# CT_v02.net
KiCad netlist of a schematic drawn in Altium Designer
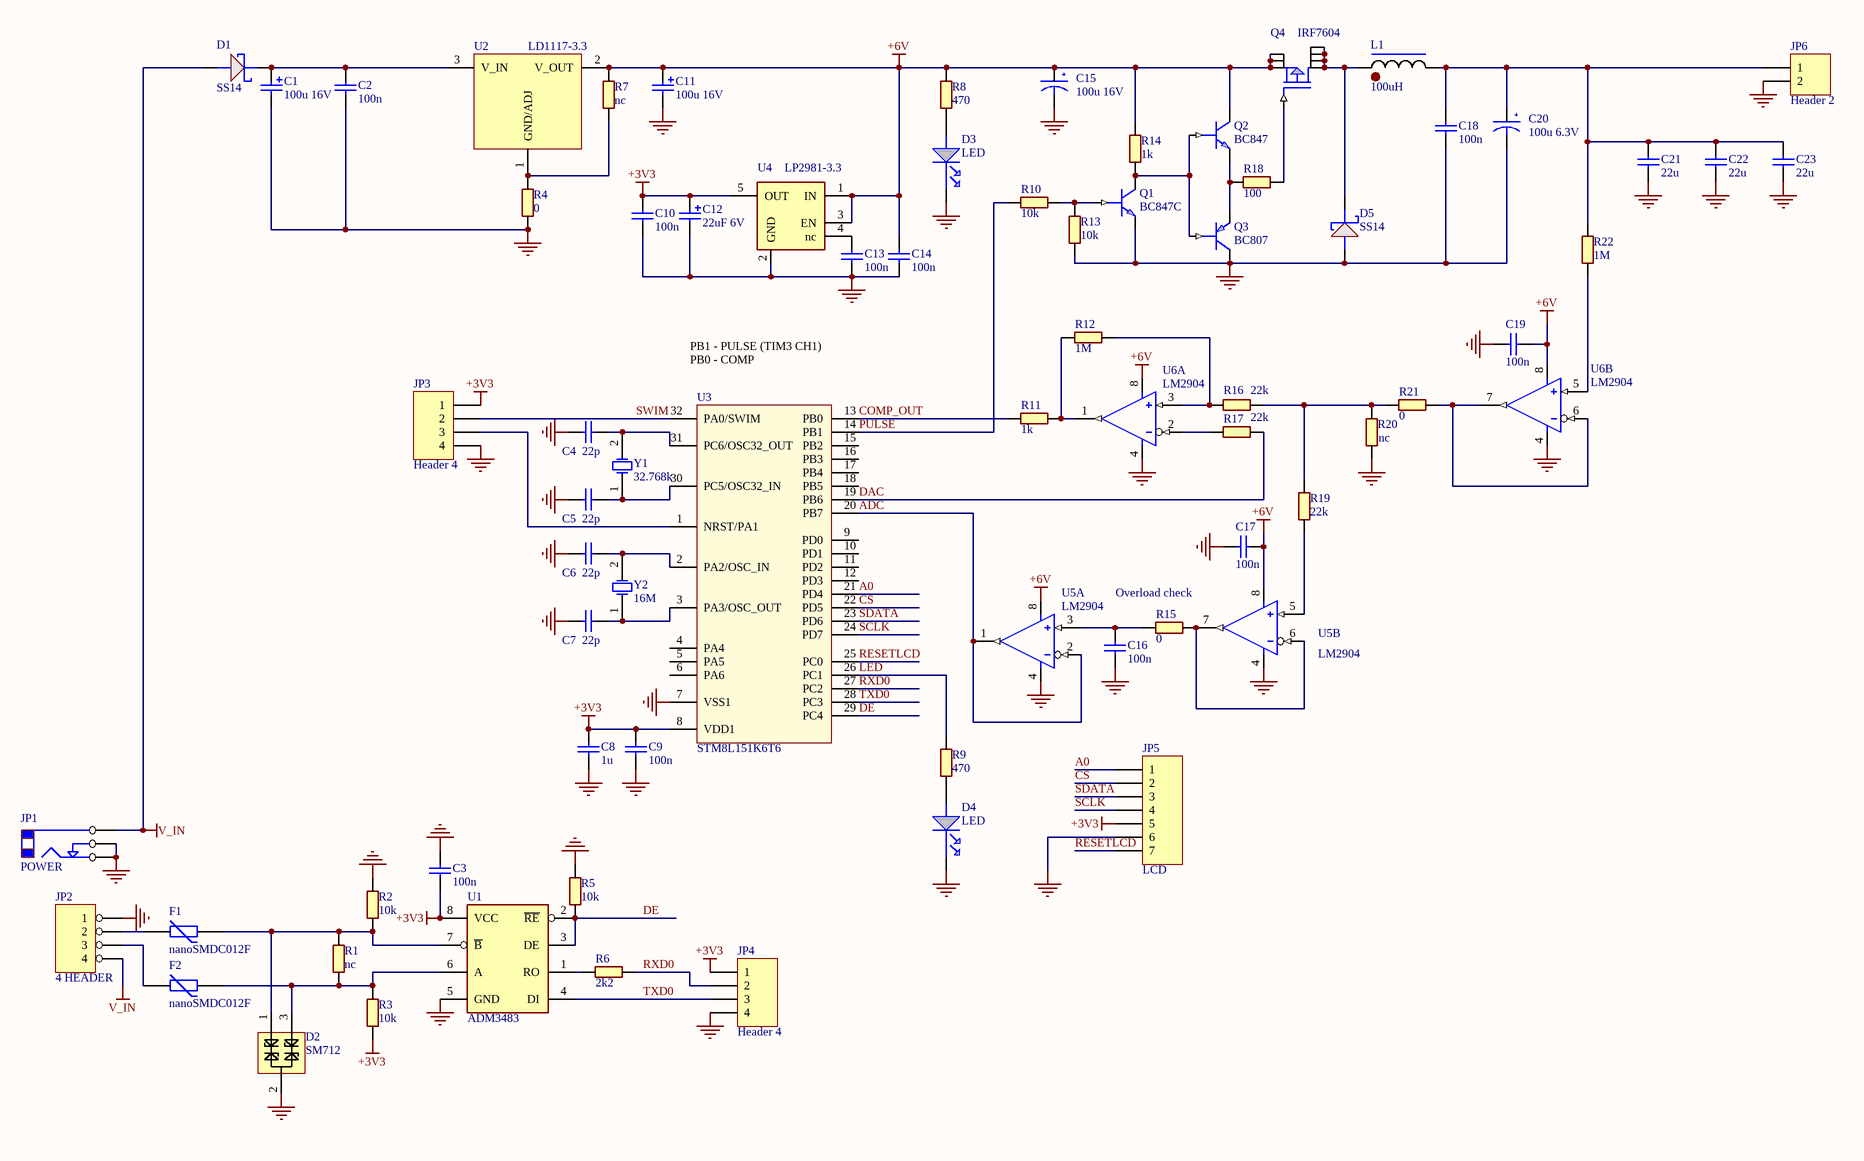
[diagram p0: CT_v02.SchDoc]

(export (version "E")
  (design (tool "Eeschema 10.0.6"))
  (components
    (comp (ref "C1") (value "100u 16V") (footprint "C_TANTAL_D") (libsource (lib "Discrete") (part "CAPP")))
    (comp (ref "C2") (value "100n") (footprint "C-0603") (libsource (lib "Discrete") (part "CAPN")))
    (comp (ref "C3") (value "100n") (footprint "C-0603") (libsource (lib "Discrete") (part "CAPN")))
    (comp (ref "C4") (value "22p") (footprint "C-0603") (libsource (lib "Discrete") (part "CAPN")))
    (comp (ref "C5") (value "22p") (footprint "C-0603") (libsource (lib "Discrete") (part "CAPN")))
    (comp (ref "C6") (value "22p") (footprint "C-0603") (libsource (lib "Discrete") (part "CAPN")))
    (comp (ref "C7") (value "22p") (footprint "C-0603") (libsource (lib "Discrete") (part "CAPN")))
    (comp (ref "C8") (value "1u") (footprint "C-0603") (libsource (lib "Discrete") (part "CAPN")))
    (comp (ref "C9") (value "100n") (footprint "C-0603") (libsource (lib "Discrete") (part "CAPN")))
    (comp (ref "C10") (value "100n") (footprint "C-0603") (libsource (lib "Discrete") (part "CAPN")))
    (comp (ref "C11") (value "100u 16V") (footprint "C_TANTAL_D") (libsource (lib "Discrete") (part "CAPP")))
    (comp (ref "C12") (value "22uF 6V") (footprint "C_TANTAL_A") (libsource (lib "Discrete") (part "CAPP")))
    (comp (ref "C13") (value "100n") (footprint "C-0603") (libsource (lib "Discrete") (part "CAPN")))
    (comp (ref "C14") (value "100n") (footprint "C-0603") (libsource (lib "Discrete") (part "CAPN")))
    (comp (ref "C15")
      (value "100u 16V")
      (footprint "C_TANTAL_D")
      (libsource (lib "Discrete") (part "C-EL-DIP"))
    )
    (comp (ref "C16") (value "100n") (footprint "C-0603") (libsource (lib "Discrete") (part "CAPN")))
    (comp (ref "C17") (value "100n") (footprint "C-0603") (libsource (lib "Discrete") (part "CAPN")))
    (comp (ref "C18") (value "100n") (footprint "C-0603") (libsource (lib "Discrete") (part "CAPN")))
    (comp (ref "C19") (value "100n") (footprint "C-0603") (libsource (lib "Discrete") (part "CAPN")))
    (comp (ref "C20")
      (value "100u 6.3V")
      (footprint "C_TANTAL_B")
      (libsource (lib "Discrete") (part "C-EL-DIP"))
    )
    (comp (ref "C21") (value "22u") (footprint "C-1206") (libsource (lib "Discrete") (part "CAPN")))
    (comp (ref "C22") (value "22u") (footprint "C-1206") (libsource (lib "Discrete") (part "CAPN")))
    (comp (ref "C23") (value "22u") (footprint "C-1206") (libsource (lib "Discrete") (part "CAPN")))
    (comp (ref "D1") (value "SS14") (footprint "D-SMA") (libsource (lib "Discrete") (part "DIODE SCHOTTKY")))
    (comp (ref "D2") (value "SM712") (footprint "SOT-23") (libsource (lib "ul2016") (part "SM712")))
    (comp (ref "D3") (value "LED") (footprint "LED_0805") (libsource (lib "Discrete") (part "LED")))
    (comp (ref "D4") (value "LED") (footprint "LED_0805") (libsource (lib "Discrete") (part "LED")))
    (comp (ref "D5") (value "SS14") (footprint "D-SMA") (libsource (lib "Discrete") (part "DIODE SCHOTTKY")))
    (comp (ref "F1") (value "nanoSMDC012F") (footprint "R-1206") (libsource (lib "ul2016") (part "VARISTOR")))
    (comp (ref "F2") (value "nanoSMDC012F") (footprint "R-1206") (libsource (lib "ul2016") (part "VARISTOR")))
    (comp (ref "JP1")
      (value "POWER")
      (footprint "DC-140-003_3")
      (libsource (lib "Connectors$switces") (part "POWER"))
    )
    (comp (ref "JP2")
      (value "4 HEADER")
      (footprint "TERMINAL4_3")
      (description "4 Pin Header")
      (libsource (lib "Connectors$switces") (part "4 HEADER"))
    )
    (comp (ref "JP3")
      (value "Header 4")
      (footprint "PLS1-4")
      (description "Header, 4-Pin")
      (libsource (lib "Miscellaneous Connectors") (part "Header 4"))
    )
    (comp (ref "JP4")
      (value "Header 4")
      (footprint "PLS1-4")
      (description "Header, 4-Pin")
      (libsource (lib "") (part "Header 4_1"))
    )
    (comp (ref "JP5")
      (value "LCD")
      (footprint "PLS1-7")
      (description "Header, 7-Pin")
      (libsource (lib "Miscellaneous Connectors") (part "Header 7"))
    )
    (comp (ref "JP6")
      (value "Header 2")
      (footprint "TERMINAL2_1")
      (description "Header, 2-Pin")
      (libsource (lib "Miscellaneous Connectors") (part "Header 2"))
    )
    (comp (ref "L1") (value "100uH") (footprint "SND-0705_3") (libsource (lib "Discrete") (part "L*")))
    (comp (ref "Q1") (value "BC847C") (footprint "SOT-23") (libsource (lib "Discrete") (part "NPN")))
    (comp (ref "Q2") (value "BC847") (footprint "SOT-23") (libsource (lib "Discrete") (part "NPN")))
    (comp (ref "Q3") (value "BC807") (footprint "SOT-23") (libsource (lib "Discrete") (part "PNP")))
    (comp (ref "Q4")
      (value "IRF7604")
      (footprint "SSOP-8")
      (libsource (lib "Discrete") (part "MOSFET_P_8pins"))
    )
    (comp (ref "R1") (value "nc") (footprint "R-0603") (libsource (lib "Discrete") (part "RES")))
    (comp (ref "R2") (value "10k") (footprint "R-0603") (libsource (lib "") (part "RES_2")))
    (comp (ref "R3") (value "10k") (footprint "R-0603") (libsource (lib "Discrete") (part "RES")))
    (comp (ref "R4") (value "0") (footprint "R-0603") (libsource (lib "") (part "RES_2")))
    (comp (ref "R5") (value "10k") (footprint "R-0603") (libsource (lib "Discrete") (part "RES")))
    (comp (ref "R6") (value "2k2") (footprint "R-0603") (libsource (lib "") (part "RES_1")))
    (comp (ref "R7") (value "nc") (footprint "R-0603") (libsource (lib "") (part "RES_2")))
    (comp (ref "R8") (value "470") (footprint "R-0603") (libsource (lib "Discrete") (part "RES")))
    (comp (ref "R9") (value "470") (footprint "R-0603") (libsource (lib "Discrete") (part "RES")))
    (comp (ref "R10") (value "10k") (footprint "R-0603") (libsource (lib "") (part "RES_1")))
    (comp (ref "R11") (value "1k") (footprint "R-0603") (libsource (lib "") (part "RES_1")))
    (comp (ref "R12") (value "1M") (footprint "R-0603") (libsource (lib "") (part "RES_1")))
    (comp (ref "R13") (value "10k") (footprint "R-0603") (libsource (lib "Discrete") (part "RES")))
    (comp (ref "R14") (value "1k") (footprint "R-0603") (libsource (lib "") (part "RES_2")))
    (comp (ref "R15") (value "0") (footprint "R-0603") (libsource (lib "") (part "RES_1")))
    (comp (ref "R16") (value "22k") (footprint "R-0603") (libsource (lib "") (part "RES_1")))
    (comp (ref "R17") (value "22k") (footprint "R-0603") (libsource (lib "") (part "RES_1")))
    (comp (ref "R18") (value "100") (footprint "R-0603") (libsource (lib "") (part "RES_1")))
    (comp (ref "R19") (value "22k") (footprint "R-0603") (libsource (lib "Discrete") (part "RES")))
    (comp (ref "R20") (value "nc") (footprint "R-0603") (libsource (lib "Discrete") (part "RES")))
    (comp (ref "R21") (value "0") (footprint "R-0603") (libsource (lib "") (part "RES_1")))
    (comp (ref "R22") (value "1M") (footprint "R-0603") (libsource (lib "") (part "RES_2")))
    (comp (ref "U1") (value "ADM3483") (footprint "SO-8") (libsource (lib "ICs") (part "SN65HVD12DG4")))
    (comp (ref "U2")
      (value "LD1117-3.3")
      (footprint "SOT223")
      (libsource (lib "RFM_PS_V01") (part "LM1117_3.3"))
    )
    (comp (ref "U3") (value "STM8L151K6T6") (footprint "QFP-32") (libsource (lib "CT") (part "STM8L151K6T6")))
    (comp (ref "U4") (value "LP2981-3.3") (footprint "SOT-23-5") (libsource (lib "ICs") (part "LP2981-3.3")))
    (comp (ref "U5")
      (value "LM2904")
      (footprint "SO-8")
      (description "2 Operation amplifier")
      (libsource (lib "ICs") (part "LM2904"))
    )
    (comp (ref "U6")
      (value "LM2904")
      (footprint "SO-8")
      (description "2 Operation amplifier")
      (libsource (lib "ICs") (part "LM2904"))
    )
    (comp (ref "Y1")
      (value "32.768k")
      (footprint "KX26")
      (description "Crystal Oscillator")
      (libsource (lib "Miscellaneous Devices") (part "XTAL"))
    )
    (comp (ref "Y2")
      (value "16M")
      (footprint "HC49_3.5mm")
      (description "Crystal Oscillator")
      (libsource (lib "Miscellaneous Devices") (part "XTAL"))
    )
  )
  (nets
    (net (code "1") (name "+3V3") (class "Default")
      (node (ref "C10") (pin "1") (pinfunction "1_1") (pintype "passive"))
      (node (ref "C12") (pin "2") (pinfunction "2_2") (pintype "passive"))
      (node (ref "C3") (pin "2") (pinfunction "2_2") (pintype "passive"))
      (node (ref "C8") (pin "1") (pinfunction "1_1") (pintype "passive"))
      (node (ref "C9") (pin "1") (pinfunction "1_1") (pintype "passive"))
      (node (ref "JP3") (pin "1") (pinfunction "1_1") (pintype "passive"))
      (node (ref "JP4") (pin "1") (pinfunction "1_1") (pintype "passive"))
      (node (ref "JP5") (pin "5") (pinfunction "5_5") (pintype "passive"))
      (node (ref "R3") (pin "2") (pinfunction "2_2") (pintype "passive"))
      (node (ref "U1") (pin "8") (pinfunction "VCC_8") (pintype "passive"))
      (node (ref "U3") (pin "8") (pinfunction "VDD1_8") (pintype "passive"))
      (node (ref "U4") (pin "5") (pinfunction "OUT_5") (pintype "passive"))
    )
    (net (code "2") (name "+6V") (class "Default")
      (node (ref "C11") (pin "2") (pinfunction "2_2") (pintype "passive"))
      (node (ref "C14") (pin "1") (pinfunction "1_1") (pintype "passive"))
      (node (ref "C15") (pin "2") (pinfunction "+_2") (pintype "passive"))
      (node (ref "C17") (pin "2") (pinfunction "2_2") (pintype "passive"))
      (node (ref "C19") (pin "2") (pinfunction "2_2") (pintype "passive"))
      (node (ref "Q2") (pin "2") (pinfunction "COLLECTOR_2") (pintype "passive"))
      (node (ref "Q4") (pin "1") (pinfunction "SOURCE_1") (pintype "passive"))
      (node (ref "Q4") (pin "2") (pinfunction "SOURCE_2") (pintype "passive"))
      (node (ref "Q4") (pin "3") (pinfunction "SOURCE_3") (pintype "passive"))
      (node (ref "R14") (pin "2") (pinfunction "2_2") (pintype "passive"))
      (node (ref "R7") (pin "2") (pinfunction "2_2") (pintype "passive"))
      (node (ref "R8") (pin "1") (pinfunction "1_1") (pintype "passive"))
      (node (ref "U2") (pin "2") (pinfunction "V_OUT_2") (pintype "passive"))
      (node (ref "U4") (pin "1") (pinfunction "IN_1") (pintype "passive"))
      (node (ref "U4") (pin "3") (pinfunction "EN_3") (pintype "passive"))
      (node (ref "U5") (pin "8") (pinfunction "V+_8") (pintype "power_in"))
      (node (ref "U6") (pin "8") (pinfunction "V+_8") (pintype "power_in"))
    )
    (net (code "3") (name "/A0") (class "Default")
      (node (ref "JP5") (pin "1") (pinfunction "1_1") (pintype "passive"))
      (node (ref "U3") (pin "21") (pinfunction "PD4_21") (pintype "passive"))
    )
    (net (code "4") (name "/ADC") (class "Default")
      (node (ref "U3") (pin "20") (pinfunction "PB7_20") (pintype "passive"))
      (node (ref "U5") (pin "1") (pinfunction "OUT_1") (pintype "output"))
      (node (ref "U5") (pin "2") (pinfunction "-IN_2") (pintype "input"))
    )
    (net (code "5") (name "/COMP_OUT") (class "Default")
      (node (ref "R11") (pin "2") (pinfunction "2_2") (pintype "passive"))
      (node (ref "U3") (pin "13") (pinfunction "PB0_13") (pintype "passive"))
    )
    (net (code "6") (name "/CS") (class "Default")
      (node (ref "JP5") (pin "2") (pinfunction "2_2") (pintype "passive"))
      (node (ref "U3") (pin "22") (pinfunction "PD5_22") (pintype "passive"))
    )
    (net (code "7") (name "/DAC") (class "Default")
      (node (ref "R17") (pin "1") (pinfunction "1_1") (pintype "passive"))
      (node (ref "U3") (pin "19") (pinfunction "PB6_19") (pintype "passive"))
    )
    (net (code "8") (name "/DE") (class "Default")
      (node (ref "R5") (pin "2") (pinfunction "2_2") (pintype "passive"))
      (node (ref "U1") (pin "2") (pinfunction "~{RE}_2") (pintype "passive"))
      (node (ref "U1") (pin "3") (pinfunction "DE_3") (pintype "passive"))
      (node (ref "U3") (pin "29") (pinfunction "PC4_29") (pintype "passive"))
    )
    (net (code "9") (name "/LED") (class "Default")
      (node (ref "R9") (pin "1") (pinfunction "1_1") (pintype "passive"))
      (node (ref "U3") (pin "26") (pinfunction "PC1_26") (pintype "passive"))
    )
    (net (code "10") (name "/PULSE") (class "Default")
      (node (ref "R10") (pin "2") (pinfunction "2_2") (pintype "passive"))
      (node (ref "U3") (pin "14") (pinfunction "PB1_14") (pintype "passive"))
    )
    (net (code "11") (name "/RESETLCD") (class "Default")
      (node (ref "JP5") (pin "7") (pinfunction "7_7") (pintype "passive"))
      (node (ref "U3") (pin "25") (pinfunction "PC0_25") (pintype "passive"))
    )
    (net (code "12") (name "/RXD0") (class "Default")
      (node (ref "JP4") (pin "2") (pinfunction "2_2") (pintype "passive"))
      (node (ref "R6") (pin "1") (pinfunction "1_1") (pintype "passive"))
      (node (ref "U3") (pin "27") (pinfunction "PC2_27") (pintype "passive"))
    )
    (net (code "13") (name "/SCLK") (class "Default")
      (node (ref "JP5") (pin "4") (pinfunction "4_4") (pintype "passive"))
      (node (ref "U3") (pin "24") (pinfunction "PD7_24") (pintype "passive"))
    )
    (net (code "14") (name "/SDATA") (class "Default")
      (node (ref "JP5") (pin "3") (pinfunction "3_3") (pintype "passive"))
      (node (ref "U3") (pin "23") (pinfunction "PD6_23") (pintype "passive"))
    )
    (net (code "15") (name "/SWIM") (class "Default")
      (node (ref "JP3") (pin "2") (pinfunction "2_2") (pintype "passive"))
      (node (ref "U3") (pin "32") (pinfunction "PA0/SWIM_32") (pintype "passive"))
    )
    (net (code "16") (name "/TXD0") (class "Default")
      (node (ref "JP4") (pin "3") (pinfunction "3_3") (pintype "passive"))
      (node (ref "U1") (pin "4") (pinfunction "DI_4") (pintype "passive"))
      (node (ref "U3") (pin "28") (pinfunction "PC3_28") (pintype "passive"))
    )
    (net (code "17") (name "GND") (class "Default")
      (node (ref "C1") (pin "1") (pinfunction "1_1") (pintype "passive"))
      (node (ref "C10") (pin "2") (pinfunction "2_2") (pintype "passive"))
      (node (ref "C11") (pin "1") (pinfunction "1_1") (pintype "passive"))
      (node (ref "C12") (pin "1") (pinfunction "1_1") (pintype "passive"))
      (node (ref "C13") (pin "2") (pinfunction "2_2") (pintype "passive"))
      (node (ref "C14") (pin "2") (pinfunction "2_2") (pintype "passive"))
      (node (ref "C15") (pin "1") (pinfunction "-_1") (pintype "passive"))
      (node (ref "C16") (pin "2") (pinfunction "2_2") (pintype "passive"))
      (node (ref "C17") (pin "1") (pinfunction "1_1") (pintype "passive"))
      (node (ref "C18") (pin "2") (pinfunction "2_2") (pintype "passive"))
      (node (ref "C19") (pin "1") (pinfunction "1_1") (pintype "passive"))
      (node (ref "C2") (pin "2") (pinfunction "2_2") (pintype "passive"))
      (node (ref "C20") (pin "1") (pinfunction "-_1") (pintype "passive"))
      (node (ref "C21") (pin "2") (pinfunction "2_2") (pintype "passive"))
      (node (ref "C22") (pin "2") (pinfunction "2_2") (pintype "passive"))
      (node (ref "C23") (pin "2") (pinfunction "2_2") (pintype "passive"))
      (node (ref "C3") (pin "1") (pinfunction "1_1") (pintype "passive"))
      (node (ref "C4") (pin "1") (pinfunction "1_1") (pintype "passive"))
      (node (ref "C5") (pin "1") (pinfunction "1_1") (pintype "passive"))
      (node (ref "C6") (pin "1") (pinfunction "1_1") (pintype "passive"))
      (node (ref "C7") (pin "1") (pinfunction "1_1") (pintype "passive"))
      (node (ref "C8") (pin "2") (pinfunction "2_2") (pintype "passive"))
      (node (ref "C9") (pin "2") (pinfunction "2_2") (pintype "passive"))
      (node (ref "D2") (pin "2") (pinfunction "2_2") (pintype "passive"))
      (node (ref "D3") (pin "K") (pinfunction "CATHODE_K") (pintype "passive"))
      (node (ref "D4") (pin "K") (pinfunction "CATHODE_K") (pintype "passive"))
      (node (ref "D5") (pin "A") (pinfunction "A_A") (pintype "passive"))
      (node (ref "JP1") (pin "2") (pinfunction "C_2") (pintype "passive"))
      (node (ref "JP1") (pin "3") (pinfunction "B_3") (pintype "passive"))
      (node (ref "JP2") (pin "1") (pinfunction "1_1") (pintype "passive"))
      (node (ref "JP3") (pin "4") (pinfunction "4_4") (pintype "passive"))
      (node (ref "JP4") (pin "4") (pinfunction "4_4") (pintype "passive"))
      (node (ref "JP5") (pin "6") (pinfunction "6_6") (pintype "passive"))
      (node (ref "JP6") (pin "2") (pinfunction "2_2") (pintype "passive"))
      (node (ref "Q1") (pin "3") (pinfunction "EMITTER_3") (pintype "passive"))
      (node (ref "Q3") (pin "2") (pinfunction "COLLECTOR_2") (pintype "passive"))
      (node (ref "R13") (pin "2") (pinfunction "2_2") (pintype "passive"))
      (node (ref "R2") (pin "2") (pinfunction "2_2") (pintype "passive"))
      (node (ref "R20") (pin "2") (pinfunction "2_2") (pintype "passive"))
      (node (ref "R4") (pin "1") (pinfunction "1_1") (pintype "passive"))
      (node (ref "R5") (pin "1") (pinfunction "1_1") (pintype "passive"))
      (node (ref "U1") (pin "5") (pinfunction "GND_5") (pintype "passive"))
      (node (ref "U3") (pin "7") (pinfunction "VSS1_7") (pintype "passive"))
      (node (ref "U4") (pin "2") (pinfunction "GND_2") (pintype "passive"))
      (node (ref "U5") (pin "4") (pinfunction "V-_4") (pintype "power_in"))
      (node (ref "U6") (pin "4") (pinfunction "V-_4") (pintype "power_in"))
    )
    (net (code "18") (name "Net-(C20-+)") (class "Default")
      (node (ref "C18") (pin "1") (pinfunction "1_1") (pintype "passive"))
      (node (ref "C20") (pin "2") (pinfunction "+_2") (pintype "passive"))
      (node (ref "C21") (pin "1") (pinfunction "1_1") (pintype "passive"))
      (node (ref "C22") (pin "1") (pinfunction "1_1") (pintype "passive"))
      (node (ref "C23") (pin "1") (pinfunction "1_1") (pintype "passive"))
      (node (ref "JP6") (pin "1") (pinfunction "1_1") (pintype "passive"))
      (node (ref "L1") (pin "2") (pinfunction "2_2") (pintype "passive"))
      (node (ref "R22") (pin "2") (pinfunction "2_2") (pintype "passive"))
    )
    (net (code "19") (name "Net-(D3-ANODE)") (class "Default")
      (node (ref "D3") (pin "A") (pinfunction "ANODE_A") (pintype "passive"))
      (node (ref "R8") (pin "2") (pinfunction "2_2") (pintype "passive"))
    )
    (net (code "20") (name "Net-(D4-ANODE)") (class "Default")
      (node (ref "D4") (pin "A") (pinfunction "ANODE_A") (pintype "passive"))
      (node (ref "R9") (pin "2") (pinfunction "2_2") (pintype "passive"))
    )
    (net (code "21") (name "Net-(D5-PadK)") (class "Default")
      (node (ref "D5") (pin "K") (pinfunction "K_K") (pintype "passive"))
      (node (ref "L1") (pin "1") (pinfunction "1_1") (pintype "passive"))
      (node (ref "Q4") (pin "5") (pinfunction "DRAIN_5") (pintype "passive"))
      (node (ref "Q4") (pin "6") (pinfunction "DRAIN_6") (pintype "passive"))
      (node (ref "Q4") (pin "7") (pinfunction "DRAIN_7") (pintype "passive"))
      (node (ref "Q4") (pin "8") (pinfunction "DRAIN_8") (pintype "passive"))
    )
    (net (code "22") (name "Net-(F1-Pad1)") (class "Default")
      (node (ref "F1") (pin "1") (pinfunction "1_1") (pintype "passive"))
      (node (ref "JP2") (pin "2") (pinfunction "2_2") (pintype "passive"))
    )
    (net (code "23") (name "Net-(F2-Pad1)") (class "Default")
      (node (ref "F2") (pin "1") (pinfunction "1_1") (pintype "passive"))
      (node (ref "JP2") (pin "3") (pinfunction "3_3") (pintype "passive"))
    )
    (net (code "24") (name "Net-(Q1-BASE)") (class "Default")
      (node (ref "Q1") (pin "1") (pinfunction "BASE_1") (pintype "input"))
      (node (ref "R10") (pin "1") (pinfunction "1_1") (pintype "passive"))
      (node (ref "R13") (pin "1") (pinfunction "1_1") (pintype "passive"))
    )
    (net (code "25") (name "Net-(Q1-COLLECTOR)") (class "Default")
      (node (ref "Q1") (pin "2") (pinfunction "COLLECTOR_2") (pintype "passive"))
      (node (ref "Q2") (pin "1") (pinfunction "BASE_1") (pintype "input"))
      (node (ref "Q3") (pin "1") (pinfunction "BASE_1") (pintype "input"))
      (node (ref "R14") (pin "1") (pinfunction "1_1") (pintype "passive"))
    )
    (net (code "26") (name "Net-(Q2-EMITTER)") (class "Default")
      (node (ref "Q2") (pin "3") (pinfunction "EMITTER_3") (pintype "passive"))
      (node (ref "Q3") (pin "3") (pinfunction "EMITTER_3") (pintype "passive"))
      (node (ref "R18") (pin "2") (pinfunction "2_2") (pintype "passive"))
    )
    (net (code "27") (name "Net-(Q4-GATE)") (class "Default")
      (node (ref "Q4") (pin "4") (pinfunction "GATE_4") (pintype "input"))
      (node (ref "R18") (pin "1") (pinfunction "1_1") (pintype "passive"))
    )
    (net (code "28") (name "Net-(R16-Pad1)") (class "Default")
      (node (ref "R16") (pin "1") (pinfunction "1_1") (pintype "passive"))
      (node (ref "R19") (pin "1") (pinfunction "1_1") (pintype "passive"))
      (node (ref "R20") (pin "1") (pinfunction "1_1") (pintype "passive"))
      (node (ref "R21") (pin "2") (pinfunction "2_2") (pintype "passive"))
    )
    (net (code "29") (name "Net-(U1-A)") (class "Default")
      (node (ref "D2") (pin "3") (pinfunction "3_3") (pintype "passive"))
      (node (ref "F2") (pin "2") (pinfunction "2_2") (pintype "passive"))
      (node (ref "R1") (pin "2") (pinfunction "2_2") (pintype "passive"))
      (node (ref "R3") (pin "1") (pinfunction "1_1") (pintype "passive"))
      (node (ref "U1") (pin "6") (pinfunction "A_6") (pintype "passive"))
    )
    (net (code "30") (name "Net-(U1-RO)") (class "Default")
      (node (ref "R6") (pin "2") (pinfunction "2_2") (pintype "passive"))
      (node (ref "U1") (pin "1") (pinfunction "RO_1") (pintype "passive"))
    )
    (net (code "31") (name "Net-(U1-~{B})") (class "Default")
      (node (ref "D2") (pin "1") (pinfunction "1_1") (pintype "passive"))
      (node (ref "F1") (pin "2") (pinfunction "2_2") (pintype "passive"))
      (node (ref "R1") (pin "1") (pinfunction "1_1") (pintype "passive"))
      (node (ref "R2") (pin "1") (pinfunction "1_1") (pintype "passive"))
      (node (ref "U1") (pin "7") (pinfunction "~{B}_7") (pintype "passive"))
    )
    (net (code "32") (name "Net-(U2-GND{slash}ADJ)") (class "Default")
      (node (ref "R4") (pin "2") (pinfunction "2_2") (pintype "passive"))
      (node (ref "R7") (pin "1") (pinfunction "1_1") (pintype "passive"))
      (node (ref "U2") (pin "1") (pinfunction "GND/ADJ_1") (pintype "passive"))
    )
    (net (code "33") (name "Net-(U2-V_IN)") (class "Default")
      (node (ref "C1") (pin "2") (pinfunction "2_2") (pintype "passive"))
      (node (ref "C2") (pin "1") (pinfunction "1_1") (pintype "passive"))
      (node (ref "D1") (pin "K") (pinfunction "K_K") (pintype "passive"))
      (node (ref "U2") (pin "3") (pinfunction "V_IN_3") (pintype "passive"))
    )
    (net (code "34") (name "Net-(U3-NRST{slash}PA1)") (class "Default")
      (node (ref "JP3") (pin "3") (pinfunction "3_3") (pintype "passive"))
      (node (ref "U3") (pin "1") (pinfunction "NRST/PA1_1") (pintype "passive"))
    )
    (net (code "35") (name "Net-(U3-PA2{slash}OSC_IN)") (class "Default")
      (node (ref "C6") (pin "2") (pinfunction "2_2") (pintype "passive"))
      (node (ref "U3") (pin "2") (pinfunction "PA2/OSC_IN_2") (pintype "passive"))
      (node (ref "Y2") (pin "2") (pinfunction "OSC2_2") (pintype "passive"))
    )
    (net (code "36") (name "Net-(U3-PA3{slash}OSC_OUT)") (class "Default")
      (node (ref "C7") (pin "2") (pinfunction "2_2") (pintype "passive"))
      (node (ref "U3") (pin "3") (pinfunction "PA3/OSC_OUT_3") (pintype "passive"))
      (node (ref "Y2") (pin "1") (pinfunction "OSC1_1") (pintype "passive"))
    )
    (net (code "37") (name "Net-(U3-PC5{slash}OSC32_IN)") (class "Default")
      (node (ref "C5") (pin "2") (pinfunction "2_2") (pintype "passive"))
      (node (ref "U3") (pin "30") (pinfunction "PC5/OSC32_IN_30") (pintype "passive"))
      (node (ref "Y1") (pin "1") (pinfunction "OSC1_1") (pintype "passive"))
    )
    (net (code "38") (name "Net-(U3-PC6{slash}OSC32_OUT)") (class "Default")
      (node (ref "C4") (pin "2") (pinfunction "2_2") (pintype "passive"))
      (node (ref "U3") (pin "31") (pinfunction "PC6/OSC32_OUT_31") (pintype "passive"))
      (node (ref "Y1") (pin "2") (pinfunction "OSC2_2") (pintype "passive"))
    )
    (net (code "39") (name "Net-(U4-nc)") (class "Default")
      (node (ref "C13") (pin "1") (pinfunction "1_1") (pintype "passive"))
      (node (ref "U4") (pin "4") (pinfunction "nc_4") (pintype "passive"))
    )
    (net (code "40") (name "Net-(U5A-+IN)") (class "Default")
      (node (ref "C16") (pin "1") (pinfunction "1_1") (pintype "passive"))
      (node (ref "R15") (pin "2") (pinfunction "2_2") (pintype "passive"))
      (node (ref "U5") (pin "3") (pinfunction "+IN_3") (pintype "input"))
    )
    (net (code "41") (name "Net-(U5B-+IN)") (class "Default")
      (node (ref "R19") (pin "2") (pinfunction "2_2") (pintype "passive"))
      (node (ref "U5") (pin "5") (pinfunction "+IN_5") (pintype "input"))
    )
    (net (code "42") (name "Net-(U5B--IN)") (class "Default")
      (node (ref "R15") (pin "1") (pinfunction "1_1") (pintype "passive"))
      (node (ref "U5") (pin "6") (pinfunction "-IN_6") (pintype "input"))
      (node (ref "U5") (pin "7") (pinfunction "OUT_7") (pintype "output"))
    )
    (net (code "43") (name "Net-(U6A-+IN)") (class "Default")
      (node (ref "R12") (pin "1") (pinfunction "1_1") (pintype "passive"))
      (node (ref "R16") (pin "2") (pinfunction "2_2") (pintype "passive"))
      (node (ref "U6") (pin "3") (pinfunction "+IN_3") (pintype "input"))
    )
    (net (code "44") (name "Net-(U6A--IN)") (class "Default")
      (node (ref "R17") (pin "2") (pinfunction "2_2") (pintype "passive"))
      (node (ref "U6") (pin "2") (pinfunction "-IN_2") (pintype "input"))
    )
    (net (code "45") (name "Net-(U6A-OUT)") (class "Default")
      (node (ref "R11") (pin "1") (pinfunction "1_1") (pintype "passive"))
      (node (ref "R12") (pin "2") (pinfunction "2_2") (pintype "passive"))
      (node (ref "U6") (pin "1") (pinfunction "OUT_1") (pintype "output"))
    )
    (net (code "46") (name "Net-(U6B-+IN)") (class "Default")
      (node (ref "R22") (pin "1") (pinfunction "1_1") (pintype "passive"))
      (node (ref "U6") (pin "5") (pinfunction "+IN_5") (pintype "input"))
    )
    (net (code "47") (name "Net-(U6B--IN)") (class "Default")
      (node (ref "R21") (pin "1") (pinfunction "1_1") (pintype "passive"))
      (node (ref "U6") (pin "6") (pinfunction "-IN_6") (pintype "input"))
      (node (ref "U6") (pin "7") (pinfunction "OUT_7") (pintype "output"))
    )
    (net (code "48") (name "V_IN") (class "Default")
      (node (ref "D1") (pin "A") (pinfunction "A_A") (pintype "passive"))
      (node (ref "JP1") (pin "1") (pinfunction "A_1") (pintype "passive"))
      (node (ref "JP2") (pin "4") (pinfunction "4_4") (pintype "passive"))
    )
    (net (code "49") (name "unconnected-(U3-PA4-Pad4)") (class "Default")
      (node (ref "U3") (pin "4") (pinfunction "PA4_4") (pintype "passive"))
    )
    (net (code "50") (name "unconnected-(U3-PA5-Pad5)") (class "Default")
      (node (ref "U3") (pin "5") (pinfunction "PA5_5") (pintype "passive"))
    )
    (net (code "51") (name "unconnected-(U3-PA6-Pad6)") (class "Default")
      (node (ref "U3") (pin "6") (pinfunction "PA6_6") (pintype "passive"))
    )
    (net (code "52") (name "unconnected-(U3-PB2-Pad15)") (class "Default")
      (node (ref "U3") (pin "15") (pinfunction "PB2_15") (pintype "passive"))
    )
    (net (code "53") (name "unconnected-(U3-PB3-Pad16)") (class "Default")
      (node (ref "U3") (pin "16") (pinfunction "PB3_16") (pintype "passive"))
    )
    (net (code "54") (name "unconnected-(U3-PB4-Pad17)") (class "Default")
      (node (ref "U3") (pin "17") (pinfunction "PB4_17") (pintype "passive"))
    )
    (net (code "55") (name "unconnected-(U3-PB5-Pad18)") (class "Default")
      (node (ref "U3") (pin "18") (pinfunction "PB5_18") (pintype "passive"))
    )
    (net (code "56") (name "unconnected-(U3-PD0-Pad9)") (class "Default")
      (node (ref "U3") (pin "9") (pinfunction "PD0_9") (pintype "passive"))
    )
    (net (code "57") (name "unconnected-(U3-PD1-Pad10)") (class "Default")
      (node (ref "U3") (pin "10") (pinfunction "PD1_10") (pintype "passive"))
    )
    (net (code "58") (name "unconnected-(U3-PD2-Pad11)") (class "Default")
      (node (ref "U3") (pin "11") (pinfunction "PD2_11") (pintype "passive"))
    )
    (net (code "59") (name "unconnected-(U3-PD3-Pad12)") (class "Default")
      (node (ref "U3") (pin "12") (pinfunction "PD3_12") (pintype "passive"))
    )
  )
)
